# esp-plane-s.net
KiCad netlist of a schematic drawn in Altium Designer
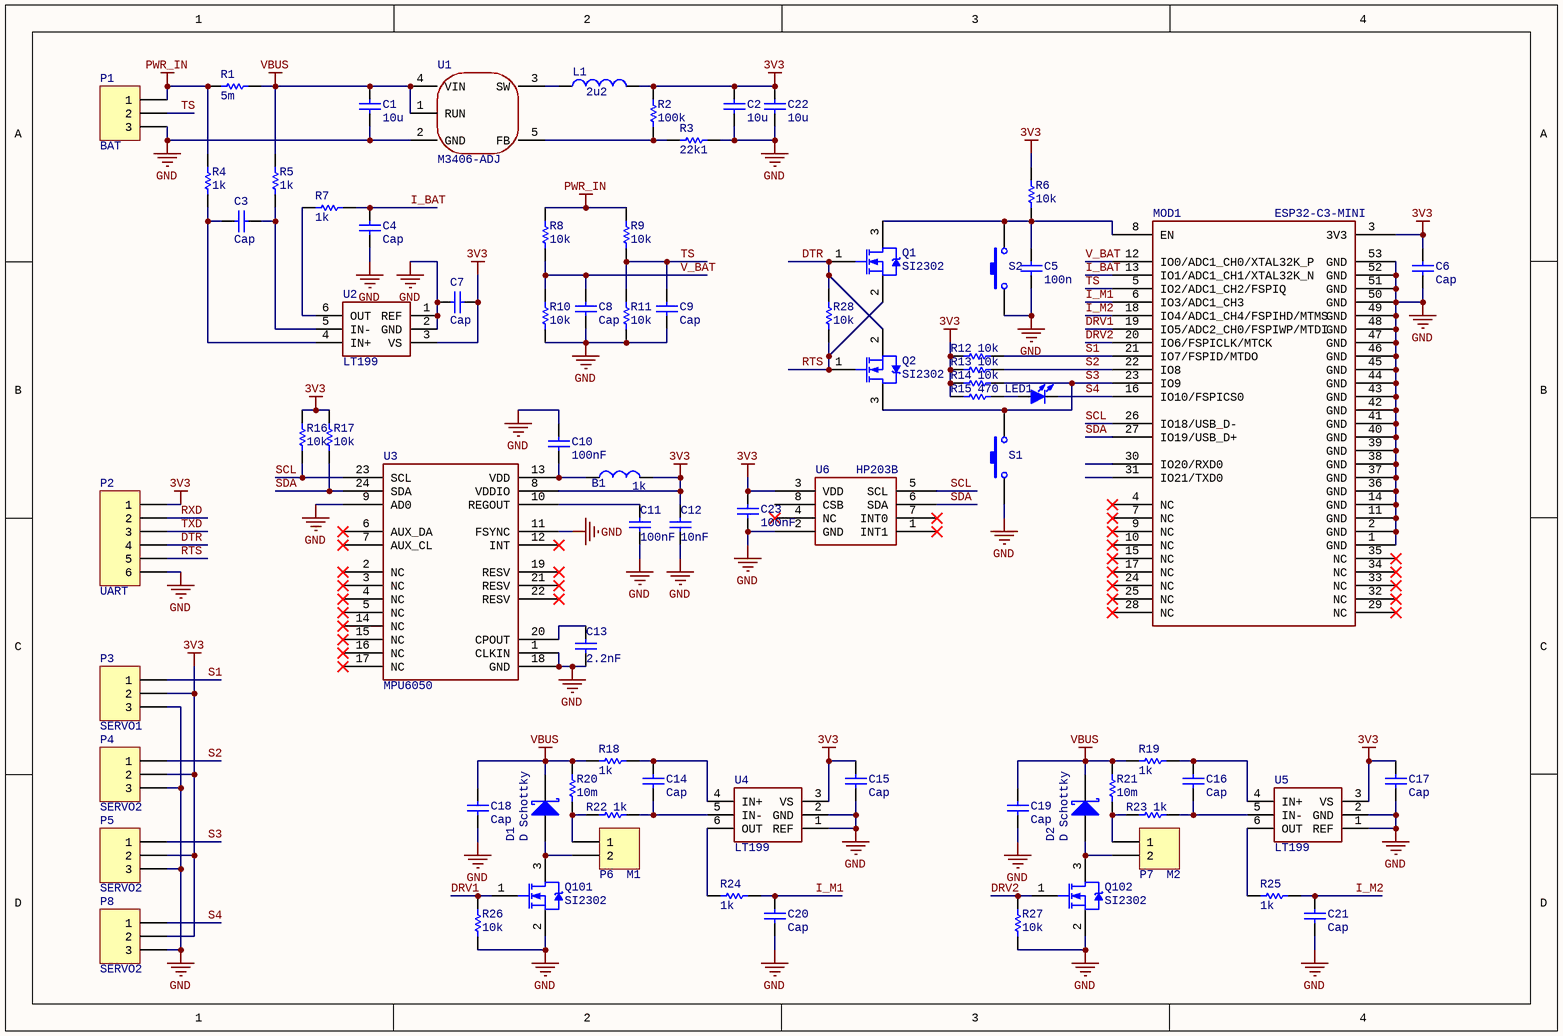
[diagram p0: esp-plane-s.SchDoc]

(export (version "E")
  (design (tool "Eeschema 10.0.6"))
  (components
    (comp (ref "B1")
      (value "1k")
      (footprint "footprints:RESC100X50X35L25N")
      (description "DCR 0.03,2A  0603")
      (fields
        (field (name "PART_NUMBER") "TY01401021")
        (field (name "MANUFACTURER_PART_NUMBER") "PZ1608U600")
      )
      (libsource (lib "*") (part "BEAD-470-100MHZ-1A-0603-BLM18PG471SN1"))
    )
    (comp (ref "C1")
      (value "10u")
      (footprint "footprints:CAPC160X80X90L30N")
      (fields
        (field (name "MPN") "TCC0603X5R106K100CT")
        (field (name "MANUFACTURER") "CCTC(三环)")
        (field (name "Comment") "Capacitor")
      )
      (libsource (lib "std_lib") (part "Capacitor"))
    )
    (comp (ref "C2")
      (value "10u")
      (footprint "footprints:CAPC160X80X90L30N")
      (fields
        (field (name "MPN") "TCC0603X5R106K100CT")
        (field (name "MANUFACTURER") "CCTC(三环)")
        (field (name "Comment") "Capacitor")
      )
      (libsource (lib "std_lib") (part "Capacitor"))
    )
    (comp (ref "C3")
      (value "Cap")
      (footprint "footprints:CAPC100X50X55L25N")
      (description "Capacitor")
      (fields (field (name "PUBLISHER") "Altium Limited"))
      (libsource (lib "Miscellaneous Devices") (part "Cap"))
    )
    (comp (ref "C4")
      (value "Cap")
      (footprint "footprints:CAPC100X50X55L25N")
      (description "Capacitor")
      (fields (field (name "PUBLISHER") "Altium Limited"))
      (libsource (lib "Miscellaneous Devices") (part "Cap"))
    )
    (comp (ref "C5")
      (value "100n")
      (footprint "footprints:CAPC100X50X55L25N")
      (fields
        (field (name "MPN") "TCC0603X5R106K100CT")
        (field (name "MANUFACTURER") "CCTC(三环)")
        (field (name "Comment") "Capacitor")
      )
      (libsource (lib "std_lib") (part "Capacitor"))
    )
    (comp (ref "C6")
      (value "Cap")
      (footprint "footprints:CAPC100X50X55L25N")
      (description "Capacitor")
      (fields (field (name "PUBLISHER") "Altium Limited"))
      (libsource (lib "Miscellaneous Devices") (part "Cap"))
    )
    (comp (ref "C7")
      (value "Cap")
      (footprint "footprints:CAPC100X50X55L25N")
      (description "Capacitor")
      (fields (field (name "PUBLISHER") "Altium Limited"))
      (libsource (lib "Miscellaneous Devices") (part "Cap"))
    )
    (comp (ref "C8")
      (value "Cap")
      (footprint "footprints:CAPC100X50X55L25N")
      (description "Capacitor")
      (fields (field (name "PUBLISHER") "Altium Limited"))
      (libsource (lib "Miscellaneous Devices") (part "Cap"))
    )
    (comp (ref "C9")
      (value "Cap")
      (footprint "footprints:CAPC100X50X55L25N")
      (description "Capacitor")
      (fields (field (name "PUBLISHER") "Altium Limited"))
      (libsource (lib "Miscellaneous Devices") (part "Cap"))
    )
    (comp (ref "C10")
      (value "100nF")
      (footprint "footprints:CAPC100X50X55L25N")
      (description "Capacitor (Semiconductor SIM Model)")
      (fields (field (name "PUBLISHER") "Altium Limited"))
      (libsource (lib "Miscellaneous Devices") (part "Cap Semi"))
    )
    (comp (ref "C11")
      (value "100nF")
      (footprint "footprints:CAPC100X50X55L25N")
      (description "Capacitor (Semiconductor SIM Model)")
      (fields (field (name "PUBLISHER") "Altium Limited"))
      (libsource (lib "Miscellaneous Devices") (part "Cap Semi"))
    )
    (comp (ref "C12")
      (value "10nF")
      (footprint "footprints:CAPC100X50X55L25N")
      (description "Capacitor (Semiconductor SIM Model)")
      (fields (field (name "PUBLISHER") "Altium Limited"))
      (libsource (lib "Miscellaneous Devices") (part "Cap Semi"))
    )
    (comp (ref "C13")
      (value "2.2nF")
      (footprint "footprints:CAPC100X50X55L25N")
      (description "Capacitor (Semiconductor SIM Model)")
      (fields (field (name "PUBLISHER") "Altium Limited"))
      (libsource (lib "Miscellaneous Devices") (part "Cap Semi"))
    )
    (comp (ref "C14")
      (value "Cap")
      (footprint "footprints:CAPC100X50X55L25N")
      (description "Capacitor")
      (fields (field (name "PUBLISHER") "Altium Limited"))
      (libsource (lib "Miscellaneous Devices") (part "Cap"))
    )
    (comp (ref "C15")
      (value "Cap")
      (footprint "footprints:CAPC100X50X55L25N")
      (description "Capacitor")
      (fields (field (name "PUBLISHER") "Altium Limited"))
      (libsource (lib "Miscellaneous Devices") (part "Cap"))
    )
    (comp (ref "C16")
      (value "Cap")
      (footprint "footprints:CAPC100X50X55L25N")
      (description "Capacitor")
      (fields (field (name "PUBLISHER") "Altium Limited"))
      (libsource (lib "Miscellaneous Devices") (part "Cap"))
    )
    (comp (ref "C17")
      (value "Cap")
      (footprint "footprints:CAPC100X50X55L25N")
      (description "Capacitor")
      (fields (field (name "PUBLISHER") "Altium Limited"))
      (libsource (lib "Miscellaneous Devices") (part "Cap"))
    )
    (comp (ref "C18")
      (value "Cap")
      (footprint "footprints:CAPC160X80X90L30N")
      (description "Capacitor")
      (fields (field (name "PUBLISHER") "Altium Limited"))
      (libsource (lib "Miscellaneous Devices") (part "Cap"))
    )
    (comp (ref "C19")
      (value "Cap")
      (footprint "footprints:CAPC160X80X90L30N")
      (description "Capacitor")
      (fields (field (name "PUBLISHER") "Altium Limited"))
      (libsource (lib "Miscellaneous Devices") (part "Cap"))
    )
    (comp (ref "C20")
      (value "Cap")
      (footprint "footprints:CAPC100X50X55L25N")
      (description "Capacitor")
      (fields (field (name "PUBLISHER") "Altium Limited"))
      (libsource (lib "Miscellaneous Devices") (part "Cap"))
    )
    (comp (ref "C21")
      (value "Cap")
      (footprint "footprints:CAPC100X50X55L25N")
      (description "Capacitor")
      (fields (field (name "PUBLISHER") "Altium Limited"))
      (libsource (lib "Miscellaneous Devices") (part "Cap"))
    )
    (comp (ref "C22")
      (value "10u")
      (footprint "footprints:CAPC160X80X90L30N")
      (fields
        (field (name "MPN") "TCC0603X5R106K100CT")
        (field (name "MANUFACTURER") "CCTC(三环)")
        (field (name "Comment") "Capacitor")
      )
      (libsource (lib "std_lib") (part "Capacitor"))
    )
    (comp (ref "C23")
      (value "100nF")
      (footprint "footprints:CAPC100X50X55L25N")
      (description "Capacitor (Semiconductor SIM Model)")
      (fields (field (name "PUBLISHER") "Altium Limited"))
      (libsource (lib "Miscellaneous Devices") (part "Cap Semi"))
    )
    (comp (ref "D1")
      (value "D Schottky")
      (footprint "footprints:SOD-523")
      (description "Schottky Diode")
      (fields (field (name "PUBLISHER") "Altium Limited"))
      (libsource (lib "Miscellaneous Devices") (part "D Schottky"))
    )
    (comp (ref "D2")
      (value "D Schottky")
      (footprint "footprints:SOD-523")
      (description "Schottky Diode")
      (fields (field (name "PUBLISHER") "Altium Limited"))
      (libsource (lib "Miscellaneous Devices") (part "D Schottky"))
    )
    (comp (ref "L1")
      (value "2u2")
      (footprint "footprints:INDC200X160X105L60N")
      (fields
        (field (name "MPN") "SFE201610-2R2M")
        (field (name "MANUFACTURER") "DDY(德立)")
        (field (name "Comment") "Inductor")
      )
      (libsource (lib "std_lib") (part "Inductor"))
    )
    (comp (ref "LED1")
      (value "蓝灯 正贴")
      (footprint "footprints:LEDC100X50X45L25N")
      (description "贴片LED")
      (libsource (lib "mcontroller") (part "LED-SMD"))
    )
    (comp (ref "MOD1")
      (value "ESP32-C3-MINI")
      (footprint "footprints:ESP32-C3-MINI-1U")
      (libsource (lib "Sch") (part "ESP32-C3-MINI"))
    )
    (comp (ref "P1")
      (value "BAT")
      (footprint "footprints:BC-1-319")
      (description "Header, 3-Pin")
      (fields (field (name "PUBLISHER") "Altium Limited"))
      (libsource (lib "Miscellaneous Connectors") (part "Header 3"))
    )
    (comp (ref "P2")
      (value "UART")
      (footprint "HDR1X6")
      (description "Header, 6-Pin")
      (fields (field (name "PUBLISHER") "Altium Limited"))
      (libsource (lib "Miscellaneous Connectors") (part "Header 6"))
    )
    (comp (ref "P3")
      (value "SERVO1")
      (footprint "footprints:FPC-SMD_3P-P1.25_DEALON_1.25-3PS-1")
      (description "Header, 3-Pin")
      (fields (field (name "PUBLISHER") "Altium Limited"))
      (libsource (lib "Miscellaneous Connectors") (part "Header 3"))
    )
    (comp (ref "P4")
      (value "SERVO2")
      (footprint "footprints:FPC-SMD_3P-P1.25_DEALON_1.25-3PS-1")
      (description "Header, 3-Pin")
      (fields (field (name "PUBLISHER") "Altium Limited"))
      (libsource (lib "Miscellaneous Connectors") (part "Header 3"))
    )
    (comp (ref "P5")
      (value "SERVO2")
      (footprint "footprints:FPC-SMD_3P-P1.25_DEALON_1.25-3PS-1")
      (description "Header, 3-Pin")
      (fields (field (name "PUBLISHER") "Altium Limited"))
      (libsource (lib "Miscellaneous Connectors") (part "Header 3"))
    )
    (comp (ref "P6")
      (value "M1")
      (footprint "footprints:CONN-SMD_2P-P1.25_DEALON_1.25-2PS")
      (description "Header, 2-Pin")
      (fields (field (name "PUBLISHER") "Altium Limited"))
      (libsource (lib "Miscellaneous Connectors") (part "Header 2"))
    )
    (comp (ref "P7")
      (value "M2")
      (footprint "footprints:CONN-SMD_2P-P1.25_DEALON_1.25-2PS")
      (description "Header, 2-Pin")
      (fields (field (name "PUBLISHER") "Altium Limited"))
      (libsource (lib "Miscellaneous Connectors") (part "Header 2"))
    )
    (comp (ref "P8")
      (value "SERVO2")
      (footprint "footprints:FPC-SMD_3P-P1.25_DEALON_1.25-3PS-1")
      (description "Header, 3-Pin")
      (fields (field (name "PUBLISHER") "Altium Limited"))
      (libsource (lib "Miscellaneous Connectors") (part "Header 3"))
    )
    (comp (ref "Q1")
      (value "SI2302")
      (footprint "footprints:SOT23-3P95_237X111L52X43N")
      (description "N-Channel Power MOSFET")
      (fields (field (name "PUBLISHER") "Altium Limited"))
      (libsource (lib "Sch") (part "NMOS-2"))
    )
    (comp (ref "Q2")
      (value "SI2302")
      (footprint "footprints:SOT23-3P95_237X111L52X43N")
      (description "N-Channel Power MOSFET")
      (fields (field (name "PUBLISHER") "Altium Limited"))
      (libsource (lib "Sch") (part "NMOS-2"))
    )
    (comp (ref "Q101")
      (value "SI2302")
      (footprint "footprints:SOT23-3P95_237X111L52X43N")
      (description "N-Channel Power MOSFET")
      (fields (field (name "PUBLISHER") "Altium Limited"))
      (libsource (lib "Sch") (part "NMOS-2"))
    )
    (comp (ref "Q102")
      (value "SI2302")
      (footprint "footprints:SOT23-3P95_237X111L52X43N")
      (description "N-Channel Power MOSFET")
      (fields (field (name "PUBLISHER") "Altium Limited"))
      (libsource (lib "Sch") (part "NMOS-2"))
    )
    (comp (ref "R1")
      (value "5m")
      (footprint "footprints:RES 0603/1608")
      (description "Resistor")
      (fields (field (name "PUBLISHER") "Altium Limited"))
      (libsource (lib "Miscellaneous Devices") (part "Res1"))
    )
    (comp (ref "R2")
      (value "100k")
      (footprint "footprints:RESC100X50X35L25N")
      (fields
        (field (name "MPN") "RTT021003FTH")
        (field (name "MANUFACTURER") "RALEC(旺诠)")
        (field (name "Comment") "Resistor")
      )
      (libsource (lib "std_lib") (part "Resistor"))
    )
    (comp (ref "R3")
      (value "22k1")
      (footprint "footprints:RESC100X50X35L25N")
      (fields
        (field (name "MPN") "RTT022212FTH")
        (field (name "MANUFACTURER") "RALEC(旺诠)")
        (field (name "Comment") "Resistor")
      )
      (libsource (lib "std_lib") (part "Resistor"))
    )
    (comp (ref "R4")
      (value "1k")
      (footprint "footprints:RESC100X50X35L25N")
      (description "Resistor")
      (fields (field (name "PUBLISHER") "Altium Limited"))
      (libsource (lib "Miscellaneous Devices") (part "Res1"))
    )
    (comp (ref "R5")
      (value "1k")
      (footprint "footprints:RESC100X50X35L25N")
      (description "Resistor")
      (fields (field (name "PUBLISHER") "Altium Limited"))
      (libsource (lib "Miscellaneous Devices") (part "Res1"))
    )
    (comp (ref "R6")
      (value "10k")
      (footprint "footprints:RESC100X50X35L25N")
      (fields
        (field (name "MPN") "RTT022212FTH")
        (field (name "MANUFACTURER") "RALEC(旺诠)")
        (field (name "Comment") "Resistor")
      )
      (libsource (lib "std_lib") (part "Resistor"))
    )
    (comp (ref "R7")
      (value "1k")
      (footprint "footprints:RESC100X50X35L25N")
      (description "Resistor")
      (fields (field (name "PUBLISHER") "Altium Limited"))
      (libsource (lib "Miscellaneous Devices") (part "Res1"))
    )
    (comp (ref "R8")
      (value "10k")
      (footprint "footprints:RESC100X50X35L25N")
      (description "Resistor")
      (fields (field (name "PUBLISHER") "Altium Limited"))
      (libsource (lib "Miscellaneous Devices") (part "Res1"))
    )
    (comp (ref "R9")
      (value "10k")
      (footprint "footprints:RESC100X50X35L25N")
      (description "Resistor")
      (fields (field (name "PUBLISHER") "Altium Limited"))
      (libsource (lib "Miscellaneous Devices") (part "Res1"))
    )
    (comp (ref "R10")
      (value "10k")
      (footprint "footprints:RESC100X50X35L25N")
      (description "Resistor")
      (fields (field (name "PUBLISHER") "Altium Limited"))
      (libsource (lib "Miscellaneous Devices") (part "Res1"))
    )
    (comp (ref "R11")
      (value "10k")
      (footprint "footprints:RESC100X50X35L25N")
      (description "Resistor")
      (fields (field (name "PUBLISHER") "Altium Limited"))
      (libsource (lib "Miscellaneous Devices") (part "Res1"))
    )
    (comp (ref "R12")
      (value "10k")
      (footprint "footprints:RESC100X50X35L25N")
      (fields
        (field (name "MPN") "RTT02471JTH")
        (field (name "MANUFACTURER") "RALEC(旺诠)")
        (field (name "Comment") "Resistor")
      )
      (libsource (lib "std_lib") (part "Resistor"))
    )
    (comp (ref "R13")
      (value "10k")
      (footprint "footprints:RESC100X50X35L25N")
      (fields
        (field (name "MPN") "RTT02471JTH")
        (field (name "MANUFACTURER") "RALEC(旺诠)")
        (field (name "Comment") "Resistor")
      )
      (libsource (lib "std_lib") (part "Resistor"))
    )
    (comp (ref "R14")
      (value "10k")
      (footprint "footprints:RESC100X50X35L25N")
      (fields
        (field (name "MPN") "RTT02471JTH")
        (field (name "MANUFACTURER") "RALEC(旺诠)")
        (field (name "Comment") "Resistor")
      )
      (libsource (lib "std_lib") (part "Resistor"))
    )
    (comp (ref "R15")
      (value "470")
      (footprint "footprints:RESC100X50X35L25N")
      (fields
        (field (name "MPN") "RTT02471JTH")
        (field (name "MANUFACTURER") "RALEC(旺诠)")
        (field (name "Comment") "Resistor")
      )
      (libsource (lib "std_lib") (part "Resistor"))
    )
    (comp (ref "R16")
      (value "10k")
      (footprint "footprints:RESC100X50X35L25N")
      (description "RES SMD 4.7K OHM 5% 1/16W 0402")
      (fields (field (name "MANUFACTURER") "Yageo") (field (name "PART NUMBER") "RC0402JR-074K7L"))
      (libsource (lib "am-resistor") (part "RC0402JR-074K7L"))
    )
    (comp (ref "R17")
      (value "10k")
      (footprint "footprints:RESC100X50X35L25N")
      (description "RES SMD 4.7K OHM 5% 1/16W 0402")
      (fields (field (name "MANUFACTURER") "Yageo") (field (name "PART NUMBER") "RC0402JR-074K7L"))
      (libsource (lib "am-resistor") (part "RC0402JR-074K7L"))
    )
    (comp (ref "R18")
      (value "1k")
      (footprint "footprints:RESC100X50X35L25N")
      (description "Resistor")
      (fields (field (name "PUBLISHER") "Altium Limited"))
      (libsource (lib "Miscellaneous Devices") (part "Res1"))
    )
    (comp (ref "R19")
      (value "1k")
      (footprint "footprints:RESC100X50X35L25N")
      (description "Resistor")
      (fields (field (name "PUBLISHER") "Altium Limited"))
      (libsource (lib "Miscellaneous Devices") (part "Res1"))
    )
    (comp (ref "R20")
      (value "10m")
      (footprint "footprints:RES 0603/1608")
      (description "Resistor")
      (fields (field (name "PUBLISHER") "Altium Limited"))
      (libsource (lib "Miscellaneous Devices") (part "Res1"))
    )
    (comp (ref "R21")
      (value "10m")
      (footprint "footprints:RES 0603/1608")
      (description "Resistor")
      (fields (field (name "PUBLISHER") "Altium Limited"))
      (libsource (lib "Miscellaneous Devices") (part "Res1"))
    )
    (comp (ref "R22")
      (value "1k")
      (footprint "footprints:RESC100X50X35L25N")
      (description "Resistor")
      (fields (field (name "PUBLISHER") "Altium Limited"))
      (libsource (lib "Miscellaneous Devices") (part "Res1"))
    )
    (comp (ref "R23")
      (value "1k")
      (footprint "footprints:RESC100X50X35L25N")
      (description "Resistor")
      (fields (field (name "PUBLISHER") "Altium Limited"))
      (libsource (lib "Miscellaneous Devices") (part "Res1"))
    )
    (comp (ref "R24")
      (value "1k")
      (footprint "footprints:RESC100X50X35L25N")
      (description "Resistor")
      (fields (field (name "PUBLISHER") "Altium Limited"))
      (libsource (lib "Miscellaneous Devices") (part "Res1"))
    )
    (comp (ref "R25")
      (value "1k")
      (footprint "footprints:RESC100X50X35L25N")
      (description "Resistor")
      (fields (field (name "PUBLISHER") "Altium Limited"))
      (libsource (lib "Miscellaneous Devices") (part "Res1"))
    )
    (comp (ref "R26")
      (value "10k")
      (footprint "footprints:RESC100X50X35L25N")
      (description "Resistor")
      (fields (field (name "PUBLISHER") "Altium Limited"))
      (libsource (lib "Miscellaneous Devices") (part "Res1"))
    )
    (comp (ref "R27")
      (value "10k")
      (footprint "footprints:RESC100X50X35L25N")
      (description "Resistor")
      (fields (field (name "PUBLISHER") "Altium Limited"))
      (libsource (lib "Miscellaneous Devices") (part "Res1"))
    )
    (comp (ref "R28")
      (value "10k")
      (footprint "footprints:RESC100X50X35L25N")
      (fields
        (field (name "MPN") "RTT02471JTH")
        (field (name "MANUFACTURER") "RALEC(旺诠)")
        (field (name "Comment") "Resistor")
      )
      (libsource (lib "std_lib") (part "Resistor"))
    )
    (comp (ref "S1")
      (value "KEY")
      (footprint "footprints:KEY-3*4")
      (description "Switch")
      (fields (field (name "PUBLISHER") "Altium Limited"))
      (libsource (lib "Miscellaneous Devices") (part "SW-PB"))
    )
    (comp (ref "S2")
      (value "KEY")
      (footprint "footprints:KEY-3*4")
      (description "Switch")
      (fields (field (name "PUBLISHER") "Altium Limited"))
      (libsource (lib "Miscellaneous Devices") (part "SW-PB"))
    )
    (comp (ref "U1")
      (value "M3406-ADJ")
      (footprint "footprints:SOT23-5P95_280X110L37X40N")
      (description "Vin=2V~6V,800mA,DCDC")
      (fields (field (name "MANUFACTURER") "西安航天民芯"))
      (libsource (lib "Sch") (part "M3406-ADJ"))
    )
    (comp (ref "U2")
      (value "LT199")
      (footprint "footprints:SC-70-6_L2.0-W1.3-P0.65-LS2.2-BL")
      (libsource (lib "") (part "LT199_SC70-6L_1"))
    )
    (comp (ref "U3")
      (value "MPU6050")
      (footprint "footprints:IMU-3000")
      (libsource (lib "Sch") (part "MPU6050"))
    )
    (comp (ref "U4")
      (value "LT199")
      (footprint "footprints:SC-70-6_L2.0-W1.3-P0.65-LS2.2-BL")
      (libsource (lib "Sch") (part "LT199_SC70-6L"))
    )
    (comp (ref "U5")
      (value "LT199")
      (footprint "footprints:SC-70-6_L2.0-W1.3-P0.65-LS2.2-BL")
      (libsource (lib "Sch") (part "LT199_SC70-6L"))
    )
    (comp (ref "U6")
      (value "HP203B")
      (footprint "footprints:HP203B")
      (libsource (lib "mcontroller") (part "HP203B"))
    )
  )
  (nets
    (net (code "1") (name "/DRV1") (class "Default")
      (node (ref "MOD1") (pin "19") (pinfunction "IO5/ADC2_CH0/FSPIWP/MTDI_19") (pintype "passive"))
      (node (ref "Q101") (pin "1") (pinfunction "G_1") (pintype "passive"))
      (node (ref "R26") (pin "2") (pinfunction "2_2") (pintype "passive"))
    )
    (net (code "2") (name "/DRV2") (class "Default")
      (node (ref "MOD1") (pin "20") (pinfunction "IO6/FSPICLK/MTCK_20") (pintype "passive"))
      (node (ref "Q102") (pin "1") (pinfunction "G_1") (pintype "passive"))
      (node (ref "R27") (pin "2") (pinfunction "2_2") (pintype "passive"))
    )
    (net (code "3") (name "/DTR") (class "Default")
      (node (ref "P2") (pin "4") (pinfunction "4_4") (pintype "passive"))
      (node (ref "Q1") (pin "1") (pinfunction "G_1") (pintype "passive"))
      (node (ref "Q2") (pin "2") (pinfunction "S_2") (pintype "passive"))
      (node (ref "R28") (pin "2") (pinfunction "2_2") (pintype "passive"))
    )
    (net (code "4") (name "/I_BAT") (class "Default")
      (node (ref "C4") (pin "2") (pinfunction "2_2") (pintype "passive"))
      (node (ref "MOD1") (pin "13") (pinfunction "IO1/ADC1_CH1/XTAL32K_N_13") (pintype "passive"))
      (node (ref "R7") (pin "2") (pinfunction "2_2") (pintype "passive"))
    )
    (net (code "5") (name "/I_M1") (class "Default")
      (node (ref "C20") (pin "2") (pinfunction "2_2") (pintype "passive"))
      (node (ref "MOD1") (pin "6") (pinfunction "IO3/ADC1_CH3_6") (pintype "passive"))
      (node (ref "R24") (pin "2") (pinfunction "2_2") (pintype "passive"))
    )
    (net (code "6") (name "/I_M2") (class "Default")
      (node (ref "C21") (pin "2") (pinfunction "2_2") (pintype "passive"))
      (node (ref "MOD1") (pin "18") (pinfunction "IO4/ADC1_CH4/FSPIHD/MTMS_18") (pintype "passive"))
      (node (ref "R25") (pin "2") (pinfunction "2_2") (pintype "passive"))
    )
    (net (code "7") (name "/RTS") (class "Default")
      (node (ref "P2") (pin "5") (pinfunction "5_5") (pintype "passive"))
      (node (ref "Q1") (pin "2") (pinfunction "S_2") (pintype "passive"))
      (node (ref "Q2") (pin "1") (pinfunction "G_1") (pintype "passive"))
      (node (ref "R28") (pin "1") (pinfunction "1_1") (pintype "passive"))
    )
    (net (code "8") (name "/RXD") (class "Default")
      (node (ref "P2") (pin "2") (pinfunction "2_2") (pintype "passive"))
    )
    (net (code "9") (name "/S1") (class "Default")
      (node (ref "MOD1") (pin "21") (pinfunction "IO7/FSPID/MTDO_21") (pintype "passive"))
      (node (ref "P3") (pin "1") (pinfunction "1_1") (pintype "passive"))
      (node (ref "R12") (pin "2") (pinfunction "2_2") (pintype "passive"))
    )
    (net (code "10") (name "/S2") (class "Default")
      (node (ref "MOD1") (pin "22") (pinfunction "IO8_22") (pintype "passive"))
      (node (ref "P4") (pin "1") (pinfunction "1_1") (pintype "passive"))
      (node (ref "R13") (pin "2") (pinfunction "2_2") (pintype "passive"))
    )
    (net (code "11") (name "/S3") (class "Default")
      (node (ref "MOD1") (pin "23") (pinfunction "IO9_23") (pintype "passive"))
      (node (ref "P5") (pin "1") (pinfunction "1_1") (pintype "passive"))
      (node (ref "Q2") (pin "3") (pinfunction "D_3") (pintype "passive"))
      (node (ref "R14") (pin "2") (pinfunction "2_2") (pintype "passive"))
      (node (ref "S1") (pin "1") (pinfunction "1_1") (pintype "passive"))
    )
    (net (code "12") (name "/S4") (class "Default")
      (node (ref "LED1") (pin "C") (pinfunction "K_C") (pintype "passive"))
      (node (ref "MOD1") (pin "16") (pinfunction "IO10/FSPICS0_16") (pintype "passive"))
      (node (ref "P8") (pin "1") (pinfunction "1_1") (pintype "passive"))
    )
    (net (code "13") (name "/SCL") (class "Default")
      (node (ref "MOD1") (pin "26") (pinfunction "IO18/USB_D-_26") (pintype "passive"))
      (node (ref "R16") (pin "1") (pinfunction "1_1") (pintype "passive"))
      (node (ref "U3") (pin "23") (pinfunction "SCL_23") (pintype "passive"))
      (node (ref "U6") (pin "5") (pinfunction "SCL_5") (pintype "passive"))
    )
    (net (code "14") (name "/SDA") (class "Default")
      (node (ref "MOD1") (pin "27") (pinfunction "IO19/USB_D+_27") (pintype "passive"))
      (node (ref "R17") (pin "1") (pinfunction "1_1") (pintype "passive"))
      (node (ref "U3") (pin "24") (pinfunction "SDA_24") (pintype "passive"))
      (node (ref "U6") (pin "6") (pinfunction "SDA_6") (pintype "passive"))
    )
    (net (code "15") (name "/TS") (class "Default")
      (node (ref "C9") (pin "1") (pinfunction "1_1") (pintype "passive"))
      (node (ref "MOD1") (pin "5") (pinfunction "IO2/ADC1_CH2/FSPIQ_5") (pintype "passive"))
      (node (ref "P1") (pin "2") (pinfunction "2_2") (pintype "passive"))
      (node (ref "R11") (pin "2") (pinfunction "2_2") (pintype "passive"))
      (node (ref "R9") (pin "1") (pinfunction "1_1") (pintype "passive"))
    )
    (net (code "16") (name "/TXD") (class "Default")
      (node (ref "P2") (pin "3") (pinfunction "3_3") (pintype "passive"))
    )
    (net (code "17") (name "/V_BAT") (class "Default")
      (node (ref "C8") (pin "1") (pinfunction "1_1") (pintype "passive"))
      (node (ref "MOD1") (pin "12") (pinfunction "IO0/ADC1_CH0/XTAL32K_P_12") (pintype "passive"))
      (node (ref "R10") (pin "2") (pinfunction "2_2") (pintype "passive"))
      (node (ref "R8") (pin "1") (pinfunction "1_1") (pintype "passive"))
    )
    (net (code "18") (name "3V3") (class "Default")
      (node (ref "B1") (pin "2") (pinfunction "2_2") (pintype "passive"))
      (node (ref "C12") (pin "1") (pinfunction "1_1") (pintype "passive"))
      (node (ref "C15") (pin "2") (pinfunction "2_2") (pintype "passive"))
      (node (ref "C17") (pin "2") (pinfunction "2_2") (pintype "passive"))
      (node (ref "C2") (pin "2") (pinfunction "2_2") (pintype "passive"))
      (node (ref "C22") (pin "2") (pinfunction "2_2") (pintype "passive"))
      (node (ref "C23") (pin "1") (pinfunction "1_1") (pintype "passive"))
      (node (ref "C6") (pin "2") (pinfunction "2_2") (pintype "passive"))
      (node (ref "C7") (pin "1") (pinfunction "1_1") (pintype "passive"))
      (node (ref "L1") (pin "2") (pinfunction "2_2") (pintype "passive"))
      (node (ref "MOD1") (pin "3") (pinfunction "3V3_3") (pintype "passive"))
      (node (ref "P2") (pin "1") (pinfunction "1_1") (pintype "passive"))
      (node (ref "P3") (pin "2") (pinfunction "2_2") (pintype "passive"))
      (node (ref "P4") (pin "2") (pinfunction "2_2") (pintype "passive"))
      (node (ref "P5") (pin "2") (pinfunction "2_2") (pintype "passive"))
      (node (ref "P8") (pin "2") (pinfunction "2_2") (pintype "passive"))
      (node (ref "R12") (pin "1") (pinfunction "1_1") (pintype "passive"))
      (node (ref "R13") (pin "1") (pinfunction "1_1") (pintype "passive"))
      (node (ref "R14") (pin "1") (pinfunction "1_1") (pintype "passive"))
      (node (ref "R15") (pin "1") (pinfunction "1_1") (pintype "passive"))
      (node (ref "R16") (pin "2") (pinfunction "2_2") (pintype "passive"))
      (node (ref "R17") (pin "2") (pinfunction "2_2") (pintype "passive"))
      (node (ref "R2") (pin "2") (pinfunction "2_2") (pintype "passive"))
      (node (ref "R6") (pin "2") (pinfunction "2_2") (pintype "passive"))
      (node (ref "U2") (pin "3") (pinfunction "VS_3") (pintype "passive"))
      (node (ref "U3") (pin "8") (pinfunction "VDDIO_8") (pintype "passive"))
      (node (ref "U4") (pin "3") (pinfunction "VS_3") (pintype "passive"))
      (node (ref "U5") (pin "3") (pinfunction "VS_3") (pintype "passive"))
      (node (ref "U6") (pin "3") (pinfunction "VDD_3") (pintype "passive"))
    )
    (net (code "19") (name "GND") (class "Default")
      (node (ref "C1") (pin "1") (pinfunction "1_1") (pintype "passive"))
      (node (ref "C10") (pin "1") (pinfunction "1_1") (pintype "passive"))
      (node (ref "C11") (pin "1") (pinfunction "1_1") (pintype "passive"))
      (node (ref "C12") (pin "2") (pinfunction "2_2") (pintype "passive"))
      (node (ref "C13") (pin "1") (pinfunction "1_1") (pintype "passive"))
      (node (ref "C15") (pin "1") (pinfunction "1_1") (pintype "passive"))
      (node (ref "C17") (pin "1") (pinfunction "1_1") (pintype "passive"))
      (node (ref "C18") (pin "1") (pinfunction "1_1") (pintype "passive"))
      (node (ref "C19") (pin "1") (pinfunction "1_1") (pintype "passive"))
      (node (ref "C2") (pin "1") (pinfunction "1_1") (pintype "passive"))
      (node (ref "C20") (pin "1") (pinfunction "1_1") (pintype "passive"))
      (node (ref "C21") (pin "1") (pinfunction "1_1") (pintype "passive"))
      (node (ref "C22") (pin "1") (pinfunction "1_1") (pintype "passive"))
      (node (ref "C23") (pin "2") (pinfunction "2_2") (pintype "passive"))
      (node (ref "C4") (pin "1") (pinfunction "1_1") (pintype "passive"))
      (node (ref "C5") (pin "1") (pinfunction "1_1") (pintype "passive"))
      (node (ref "C6") (pin "1") (pinfunction "1_1") (pintype "passive"))
      (node (ref "C7") (pin "2") (pinfunction "2_2") (pintype "passive"))
      (node (ref "C8") (pin "2") (pinfunction "2_2") (pintype "passive"))
      (node (ref "C9") (pin "2") (pinfunction "2_2") (pintype "passive"))
      (node (ref "MOD1") (pin "1") (pinfunction "GND_1") (pintype "passive"))
      (node (ref "MOD1") (pin "11") (pinfunction "GND_11") (pintype "passive"))
      (node (ref "MOD1") (pin "14") (pinfunction "GND_14") (pintype "passive"))
      (node (ref "MOD1") (pin "2") (pinfunction "GND_2") (pintype "passive"))
      (node (ref "MOD1") (pin "36") (pinfunction "GND_36") (pintype "passive"))
      (node (ref "MOD1") (pin "37") (pinfunction "GND_37") (pintype "passive"))
      (node (ref "MOD1") (pin "38") (pinfunction "GND_38") (pintype "passive"))
      (node (ref "MOD1") (pin "39") (pinfunction "GND_39") (pintype "passive"))
      (node (ref "MOD1") (pin "40") (pinfunction "GND_40") (pintype "passive"))
      (node (ref "MOD1") (pin "41") (pinfunction "GND_41") (pintype "passive"))
      (node (ref "MOD1") (pin "42") (pinfunction "GND_42") (pintype "passive"))
      (node (ref "MOD1") (pin "43") (pinfunction "GND_43") (pintype "passive"))
      (node (ref "MOD1") (pin "44") (pinfunction "GND_44") (pintype "passive"))
      (node (ref "MOD1") (pin "45") (pinfunction "GND_45") (pintype "passive"))
      (node (ref "MOD1") (pin "46") (pinfunction "GND_46") (pintype "passive"))
      (node (ref "MOD1") (pin "47") (pinfunction "GND_47") (pintype "passive"))
      (node (ref "MOD1") (pin "48") (pinfunction "GND_48") (pintype "passive"))
      (node (ref "MOD1") (pin "49") (pinfunction "GND_49") (pintype "passive"))
      (node (ref "MOD1") (pin "50") (pinfunction "GND_50") (pintype "passive"))
      (node (ref "MOD1") (pin "51") (pinfunction "GND_51") (pintype "passive"))
      (node (ref "MOD1") (pin "52") (pinfunction "GND_52") (pintype "passive"))
      (node (ref "MOD1") (pin "53") (pinfunction "GND_53") (pintype "passive"))
      (node (ref "P1") (pin "3") (pinfunction "3_3") (pintype "passive"))
      (node (ref "P2") (pin "6") (pinfunction "6_6") (pintype "passive"))
      (node (ref "P3") (pin "3") (pinfunction "3_3") (pintype "passive"))
      (node (ref "P4") (pin "3") (pinfunction "3_3") (pintype "passive"))
      (node (ref "P5") (pin "3") (pinfunction "3_3") (pintype "passive"))
      (node (ref "P8") (pin "3") (pinfunction "3_3") (pintype "passive"))
      (node (ref "Q101") (pin "2") (pinfunction "S_2") (pintype "passive"))
      (node (ref "Q102") (pin "2") (pinfunction "S_2") (pintype "passive"))
      (node (ref "R10") (pin "1") (pinfunction "1_1") (pintype "passive"))
      (node (ref "R11") (pin "1") (pinfunction "1_1") (pintype "passive"))
      (node (ref "R26") (pin "1") (pinfunction "1_1") (pintype "passive"))
      (node (ref "R27") (pin "1") (pinfunction "1_1") (pintype "passive"))
      (node (ref "R3") (pin "1") (pinfunction "1_1") (pintype "passive"))
      (node (ref "S1") (pin "2") (pinfunction "2_2") (pintype "passive"))
      (node (ref "S2") (pin "2") (pinfunction "2_2") (pintype "passive"))
      (node (ref "U1") (pin "2") (pinfunction "GND_2") (pintype "passive"))
      (node (ref "U2") (pin "1") (pinfunction "REF_1") (pintype "passive"))
      (node (ref "U2") (pin "2") (pinfunction "GND_2") (pintype "passive"))
      (node (ref "U3") (pin "1") (pinfunction "CLKIN_1") (pintype "passive"))
      (node (ref "U3") (pin "11") (pinfunction "FSYNC_11") (pintype "passive"))
      (node (ref "U3") (pin "18") (pinfunction "GND_18") (pintype "passive"))
      (node (ref "U3") (pin "9") (pinfunction "AD0_9") (pintype "passive"))
      (node (ref "U4") (pin "1") (pinfunction "REF_1") (pintype "passive"))
      (node (ref "U4") (pin "2") (pinfunction "GND_2") (pintype "passive"))
      (node (ref "U5") (pin "1") (pinfunction "REF_1") (pintype "passive"))
      (node (ref "U5") (pin "2") (pinfunction "GND_2") (pintype "passive"))
      (node (ref "U6") (pin "2") (pinfunction "GND_2") (pintype "passive"))
    )
    (net (code "20") (name "Net-(D1-A)") (class "Default")
      (node (ref "D1") (pin "1") (pinfunction "A_1") (pintype "passive"))
      (node (ref "P6") (pin "2") (pinfunction "2_2") (pintype "passive"))
      (node (ref "Q101") (pin "3") (pinfunction "D_3") (pintype "passive"))
    )
    (net (code "21") (name "Net-(D2-A)") (class "Default")
      (node (ref "D2") (pin "1") (pinfunction "A_1") (pintype "passive"))
      (node (ref "P7") (pin "2") (pinfunction "2_2") (pintype "passive"))
      (node (ref "Q102") (pin "3") (pinfunction "D_3") (pintype "passive"))
    )
    (net (code "22") (name "Net-(LED1-PadA)") (class "Default")
      (node (ref "LED1") (pin "A") (pinfunction "A_A") (pintype "passive"))
      (node (ref "R15") (pin "2") (pinfunction "2_2") (pintype "passive"))
    )
    (net (code "23") (name "Net-(MOD1-EN)") (class "Default")
      (node (ref "C5") (pin "2") (pinfunction "2_2") (pintype "passive"))
      (node (ref "MOD1") (pin "8") (pinfunction "EN_8") (pintype "passive"))
      (node (ref "Q1") (pin "3") (pinfunction "D_3") (pintype "passive"))
      (node (ref "R6") (pin "1") (pinfunction "1_1") (pintype "passive"))
      (node (ref "S2") (pin "1") (pinfunction "1_1") (pintype "passive"))
    )
    (net (code "24") (name "Net-(P6-Pad1)") (class "Default")
      (node (ref "P6") (pin "1") (pinfunction "1_1") (pintype "passive"))
      (node (ref "R20") (pin "1") (pinfunction "1_1") (pintype "passive"))
      (node (ref "R22") (pin "1") (pinfunction "1_1") (pintype "passive"))
    )
    (net (code "25") (name "Net-(P7-Pad1)") (class "Default")
      (node (ref "P7") (pin "1") (pinfunction "1_1") (pintype "passive"))
      (node (ref "R21") (pin "1") (pinfunction "1_1") (pintype "passive"))
      (node (ref "R23") (pin "1") (pinfunction "1_1") (pintype "passive"))
    )
    (net (code "26") (name "Net-(U1-FB)") (class "Default")
      (node (ref "R2") (pin "1") (pinfunction "1_1") (pintype "passive"))
      (node (ref "R3") (pin "2") (pinfunction "2_2") (pintype "passive"))
      (node (ref "U1") (pin "5") (pinfunction "FB_5") (pintype "passive"))
    )
    (net (code "27") (name "Net-(U1-SW)") (class "Default")
      (node (ref "L1") (pin "1") (pinfunction "1_1") (pintype "passive"))
      (node (ref "U1") (pin "3") (pinfunction "SW_3") (pintype "passive"))
    )
    (net (code "28") (name "Net-(U2-IN+)") (class "Default")
      (node (ref "C3") (pin "1") (pinfunction "1_1") (pintype "passive"))
      (node (ref "R4") (pin "2") (pinfunction "2_2") (pintype "passive"))
      (node (ref "U2") (pin "4") (pinfunction "IN+_4") (pintype "passive"))
    )
    (net (code "29") (name "Net-(U2-IN-)") (class "Default")
      (node (ref "C3") (pin "2") (pinfunction "2_2") (pintype "passive"))
      (node (ref "R5") (pin "2") (pinfunction "2_2") (pintype "passive"))
      (node (ref "U2") (pin "5") (pinfunction "IN-_5") (pintype "passive"))
    )
    (net (code "30") (name "Net-(U2-OUT)") (class "Default")
      (node (ref "R7") (pin "1") (pinfunction "1_1") (pintype "passive"))
      (node (ref "U2") (pin "6") (pinfunction "OUT_6") (pintype "passive"))
    )
    (net (code "31") (name "Net-(U3-CPOUT)") (class "Default")
      (node (ref "C13") (pin "2") (pinfunction "2_2") (pintype "passive"))
      (node (ref "U3") (pin "20") (pinfunction "CPOUT_20") (pintype "passive"))
    )
    (net (code "32") (name "Net-(U3-REGOUT)") (class "Default")
      (node (ref "C11") (pin "2") (pinfunction "2_2") (pintype "passive"))
      (node (ref "U3") (pin "10") (pinfunction "REGOUT_10") (pintype "passive"))
    )
    (net (code "33") (name "Net-(U3-VDD)") (class "Default")
      (node (ref "B1") (pin "1") (pinfunction "1_1") (pintype "passive"))
      (node (ref "C10") (pin "2") (pinfunction "2_2") (pintype "passive"))
      (node (ref "U3") (pin "13") (pinfunction "VDD_13") (pintype "passive"))
    )
    (net (code "34") (name "Net-(U4-IN+)") (class "Default")
      (node (ref "C14") (pin "2") (pinfunction "2_2") (pintype "passive"))
      (node (ref "R18") (pin "2") (pinfunction "2_2") (pintype "passive"))
      (node (ref "U4") (pin "4") (pinfunction "IN+_4") (pintype "passive"))
    )
    (net (code "35") (name "Net-(U4-IN-)") (class "Default")
      (node (ref "C14") (pin "1") (pinfunction "1_1") (pintype "passive"))
      (node (ref "R22") (pin "2") (pinfunction "2_2") (pintype "passive"))
      (node (ref "U4") (pin "5") (pinfunction "IN-_5") (pintype "passive"))
    )
    (net (code "36") (name "Net-(U4-OUT)") (class "Default")
      (node (ref "R24") (pin "1") (pinfunction "1_1") (pintype "passive"))
      (node (ref "U4") (pin "6") (pinfunction "OUT_6") (pintype "passive"))
    )
    (net (code "37") (name "Net-(U5-IN+)") (class "Default")
      (node (ref "C16") (pin "2") (pinfunction "2_2") (pintype "passive"))
      (node (ref "R19") (pin "2") (pinfunction "2_2") (pintype "passive"))
      (node (ref "U5") (pin "4") (pinfunction "IN+_4") (pintype "passive"))
    )
    (net (code "38") (name "Net-(U5-IN-)") (class "Default")
      (node (ref "C16") (pin "1") (pinfunction "1_1") (pintype "passive"))
      (node (ref "R23") (pin "2") (pinfunction "2_2") (pintype "passive"))
      (node (ref "U5") (pin "5") (pinfunction "IN-_5") (pintype "passive"))
    )
    (net (code "39") (name "Net-(U5-OUT)") (class "Default")
      (node (ref "R25") (pin "1") (pinfunction "1_1") (pintype "passive"))
      (node (ref "U5") (pin "6") (pinfunction "OUT_6") (pintype "passive"))
    )
    (net (code "40") (name "PWR_IN") (class "Default")
      (node (ref "P1") (pin "1") (pinfunction "1_1") (pintype "passive"))
      (node (ref "R1") (pin "2") (pinfunction "2_2") (pintype "passive"))
      (node (ref "R4") (pin "1") (pinfunction "1_1") (pintype "passive"))
      (node (ref "R8") (pin "2") (pinfunction "2_2") (pintype "passive"))
      (node (ref "R9") (pin "2") (pinfunction "2_2") (pintype "passive"))
    )
    (net (code "41") (name "VBUS") (class "Default")
      (node (ref "C1") (pin "2") (pinfunction "2_2") (pintype "passive"))
      (node (ref "C18") (pin "2") (pinfunction "2_2") (pintype "passive"))
      (node (ref "C19") (pin "2") (pinfunction "2_2") (pintype "passive"))
      (node (ref "D1") (pin "2") (pinfunction "K_2") (pintype "passive"))
      (node (ref "D2") (pin "2") (pinfunction "K_2") (pintype "passive"))
      (node (ref "R1") (pin "1") (pinfunction "1_1") (pintype "passive"))
      (node (ref "R18") (pin "1") (pinfunction "1_1") (pintype "passive"))
      (node (ref "R19") (pin "1") (pinfunction "1_1") (pintype "passive"))
      (node (ref "R20") (pin "2") (pinfunction "2_2") (pintype "passive"))
      (node (ref "R21") (pin "2") (pinfunction "2_2") (pintype "passive"))
      (node (ref "R5") (pin "1") (pinfunction "1_1") (pintype "passive"))
      (node (ref "U1") (pin "1") (pinfunction "RUN_1") (pintype "passive"))
      (node (ref "U1") (pin "4") (pinfunction "VIN_4") (pintype "passive"))
    )
    (net (code "42") (name "unconnected-(MOD1-IO20{slash}RXD0-Pad30)") (class "Default")
      (node (ref "MOD1") (pin "30") (pinfunction "IO20/RXD0_30") (pintype "passive"))
    )
    (net (code "43") (name "unconnected-(MOD1-IO21{slash}TXD0-Pad31)") (class "Default")
      (node (ref "MOD1") (pin "31") (pinfunction "IO21/TXD0_31") (pintype "passive"))
    )
    (net (code "44") (name "unconnected-(MOD1-NC-Pad4)") (class "Default")
      (node (ref "MOD1") (pin "4") (pinfunction "NC_4") (pintype "passive+no_connect"))
    )
    (net (code "45") (name "unconnected-(MOD1-NC-Pad7)") (class "Default")
      (node (ref "MOD1") (pin "7") (pinfunction "NC_7") (pintype "passive+no_connect"))
    )
    (net (code "46") (name "unconnected-(MOD1-NC-Pad9)") (class "Default")
      (node (ref "MOD1") (pin "9") (pinfunction "NC_9") (pintype "passive+no_connect"))
    )
    (net (code "47") (name "unconnected-(MOD1-NC-Pad10)") (class "Default")
      (node (ref "MOD1") (pin "10") (pinfunction "NC_10") (pintype "passive+no_connect"))
    )
    (net (code "48") (name "unconnected-(MOD1-NC-Pad15)") (class "Default")
      (node (ref "MOD1") (pin "15") (pinfunction "NC_15") (pintype "passive+no_connect"))
    )
    (net (code "49") (name "unconnected-(MOD1-NC-Pad17)") (class "Default")
      (node (ref "MOD1") (pin "17") (pinfunction "NC_17") (pintype "passive+no_connect"))
    )
    (net (code "50") (name "unconnected-(MOD1-NC-Pad24)") (class "Default")
      (node (ref "MOD1") (pin "24") (pinfunction "NC_24") (pintype "passive+no_connect"))
    )
    (net (code "51") (name "unconnected-(MOD1-NC-Pad25)") (class "Default")
      (node (ref "MOD1") (pin "25") (pinfunction "NC_25") (pintype "passive+no_connect"))
    )
    (net (code "52") (name "unconnected-(MOD1-NC-Pad28)") (class "Default")
      (node (ref "MOD1") (pin "28") (pinfunction "NC_28") (pintype "passive+no_connect"))
    )
    (net (code "53") (name "unconnected-(MOD1-NC-Pad29)") (class "Default")
      (node (ref "MOD1") (pin "29") (pinfunction "NC_29") (pintype "passive+no_connect"))
    )
    (net (code "54") (name "unconnected-(MOD1-NC-Pad32)") (class "Default")
      (node (ref "MOD1") (pin "32") (pinfunction "NC_32") (pintype "passive+no_connect"))
    )
    (net (code "55") (name "unconnected-(MOD1-NC-Pad33)") (class "Default")
      (node (ref "MOD1") (pin "33") (pinfunction "NC_33") (pintype "passive+no_connect"))
    )
    (net (code "56") (name "unconnected-(MOD1-NC-Pad34)") (class "Default")
      (node (ref "MOD1") (pin "34") (pinfunction "NC_34") (pintype "passive+no_connect"))
    )
    (net (code "57") (name "unconnected-(MOD1-NC-Pad35)") (class "Default")
      (node (ref "MOD1") (pin "35") (pinfunction "NC_35") (pintype "passive+no_connect"))
    )
    (net (code "58") (name "unconnected-(U3-AUX_CL-Pad7)") (class "Default")
      (node (ref "U3") (pin "7") (pinfunction "AUX_CL_7") (pintype "passive+no_connect"))
    )
    (net (code "59") (name "unconnected-(U3-AUX_DA-Pad6)") (class "Default")
      (node (ref "U3") (pin "6") (pinfunction "AUX_DA_6") (pintype "passive+no_connect"))
    )
    (net (code "60") (name "unconnected-(U3-INT-Pad12)") (class "Default")
      (node (ref "U3") (pin "12") (pinfunction "INT_12") (pintype "passive+no_connect"))
    )
    (net (code "61") (name "unconnected-(U3-NC-Pad2)") (class "Default")
      (node (ref "U3") (pin "2") (pinfunction "NC_2") (pintype "passive+no_connect"))
    )
    (net (code "62") (name "unconnected-(U3-NC-Pad3)") (class "Default")
      (node (ref "U3") (pin "3") (pinfunction "NC_3") (pintype "passive+no_connect"))
    )
    (net (code "63") (name "unconnected-(U3-NC-Pad4)") (class "Default")
      (node (ref "U3") (pin "4") (pinfunction "NC_4") (pintype "passive+no_connect"))
    )
    (net (code "64") (name "unconnected-(U3-NC-Pad5)") (class "Default")
      (node (ref "U3") (pin "5") (pinfunction "NC_5") (pintype "passive+no_connect"))
    )
    (net (code "65") (name "unconnected-(U3-NC-Pad14)") (class "Default")
      (node (ref "U3") (pin "14") (pinfunction "NC_14") (pintype "passive+no_connect"))
    )
    (net (code "66") (name "unconnected-(U3-NC-Pad15)") (class "Default")
      (node (ref "U3") (pin "15") (pinfunction "NC_15") (pintype "passive+no_connect"))
    )
    (net (code "67") (name "unconnected-(U3-NC-Pad16)") (class "Default")
      (node (ref "U3") (pin "16") (pinfunction "NC_16") (pintype "passive+no_connect"))
    )
    (net (code "68") (name "unconnected-(U3-NC-Pad17)") (class "Default")
      (node (ref "U3") (pin "17") (pinfunction "NC_17") (pintype "passive+no_connect"))
    )
    (net (code "69") (name "unconnected-(U3-RESV-Pad19)") (class "Default")
      (node (ref "U3") (pin "19") (pinfunction "RESV_19") (pintype "passive+no_connect"))
    )
    (net (code "70") (name "unconnected-(U3-RESV-Pad21)") (class "Default")
      (node (ref "U3") (pin "21") (pinfunction "RESV_21") (pintype "passive+no_connect"))
    )
    (net (code "71") (name "unconnected-(U3-RESV-Pad22)") (class "Default")
      (node (ref "U3") (pin "22") (pinfunction "RESV_22") (pintype "passive+no_connect"))
    )
    (net (code "72") (name "unconnected-(U6-CSB-Pad8)") (class "Default")
      (node (ref "U6") (pin "8") (pinfunction "CSB_8") (pintype "passive"))
    )
    (net (code "73") (name "unconnected-(U6-INT0-Pad7)") (class "Default")
      (node (ref "U6") (pin "7") (pinfunction "INT0_7") (pintype "passive+no_connect"))
    )
    (net (code "74") (name "unconnected-(U6-INT1-Pad1)") (class "Default")
      (node (ref "U6") (pin "1") (pinfunction "INT1_1") (pintype "passive+no_connect"))
    )
    (net (code "75") (name "unconnected-(U6-NC-Pad4)") (class "Default")
      (node (ref "U6") (pin "4") (pinfunction "NC_4") (pintype "passive+no_connect"))
    )
  )
)
